# Sheet.net
KiCad netlist of a schematic drawn in Altium Designer
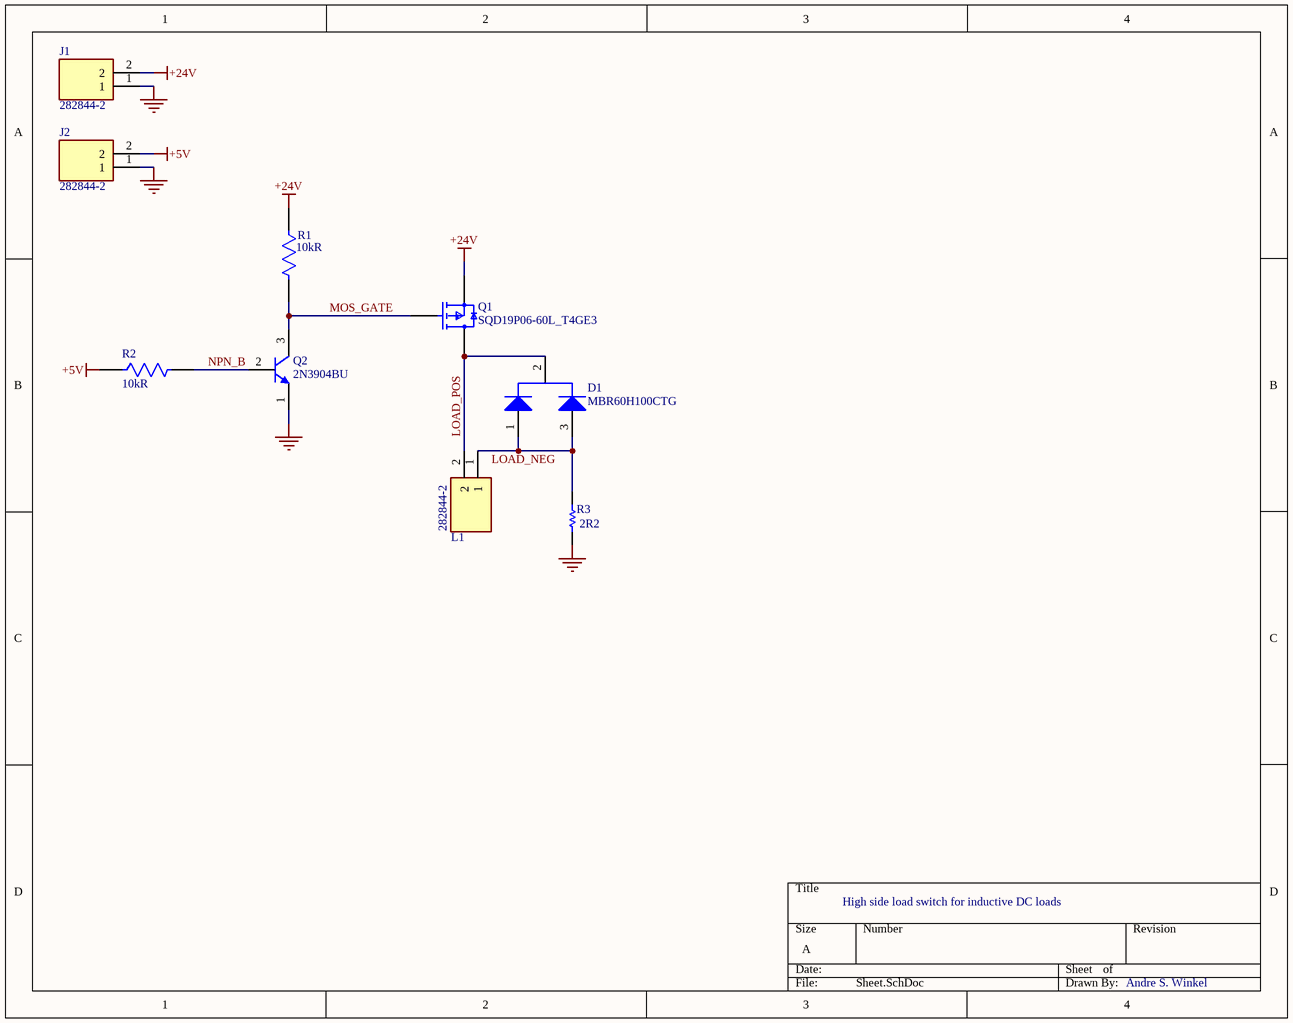
[diagram p0: Sheet.SchDoc]

(export (version "E")
  (design (tool "Eeschema 10.0.6"))
  (components
    (comp (ref "D1")
      (value "MBR60H100CTG")
      (footprint "ONSC-TO-220-3-221A-09_AF")
      (description "SWITCHMODE(TM) Power Rectifier, 100 V, 60 A, 3-Pin TO-220, Pb-Free, Tube")
      (fields (field (name "MANUFACTURER") "On Semiconductor"))
      (libsource (lib "Altium Content Vault") (part "ONSC-D-A1K2A3-3_B"))
    )
    (comp (ref "J1")
      (value "282844-2")
      (footprint "SamacSys:2828442")
      (description "Connector")
      (fields (field (name "MOUSER PART NUMBER") "571-282844-2"))
      (libsource (lib "") (part "282844-2_1"))
    )
    (comp (ref "J2")
      (value "282844-2")
      (footprint "SamacSys:2828442")
      (description "Connector")
      (fields (field (name "MOUSER PART NUMBER") "571-282844-2"))
      (libsource (lib "") (part "282844-2_1"))
    )
    (comp (ref "L1")
      (value "282844-2")
      (footprint "SamacSys:2828442")
      (description "Connector")
      (fields (field (name "MOUSER PART NUMBER") "571-282844-2"))
      (libsource (lib "*") (part "282844-2"))
    )
    (comp (ref "Q1")
      (value "SQD19P06-60L_T4GE3")
      (footprint "FP-T13-0592-MFG")
      (description "MOSFET P-CH 60V 20A TO252AA")
      (fields
        (field (name "OCTOPART") "https://octopart.com/sqd19p06-60l_t4ge3-vishay-82363551")
        (field (name "MANUFACTURER") "Vishay")
      )
      (libsource (lib "Altium Content Vault") (part "becdc239eb0611cc225413e84e4883d"))
    )
    (comp (ref "Q2")
      (value "2N3904BU")
      (footprint "FAIR-TO-92")
      (description "NPN General-Purpose Amplifier, 40 V VCEO, 0.2 A, -55 to 150 degC, 2-Pin TO-92, RoHS, Bulk")
      (fields (field (name "MANUFACTURER") "FairchildSemiconductor"))
      (libsource (lib "Altium Content Vault") (part "NPN-E1B2C3-3"))
    )
    (comp (ref "R1")
      (value "CRCW080510K0FKEA")
      (footprint "FP-CRCW0805-e3-IPC_A")
      (description "RES Thick Film, 10kΩ, 1%, 0.125W, 100ppm/°C, 0805")
      (fields (field (name "RESISTANCE") "10kR") (field (name "TOLERANCE") "1%"))
      (libsource (lib "Altium Content Vault") (part "1029c3af85768c4190bb7ad29bc67b5"))
    )
    (comp (ref "R2")
      (value "CRCW080510K0FKEA")
      (footprint "FP-CRCW0805-e3-IPC_A")
      (description "RES Thick Film, 10kΩ, 1%, 0.125W, 100ppm/°C, 0805")
      (fields (field (name "RESISTANCE") "10kR") (field (name "TOLERANCE") "1%"))
      (libsource (lib "Altium Content Vault") (part "1029c3af85768c4190bb7ad29bc67b5"))
    )
    (comp (ref "R3")
      (value "RC0402JR-072R2L")
      (footprint "RESC1005X40X25NL05T10")
      (fields (field (name "MANUFACTURER") "Yageo / Phycomp") (field (name "RESISTANCE") "2R2"))
      (libsource (lib "Altium Content Vault") (part "RES"))
    )
  )
  (nets
    (net (code "1") (name "+5V") (class "Default")
      (node (ref "J2") (pin "2") (pinfunction "2_2") (pintype "passive"))
      (node (ref "R2") (pin "1") (pinfunction "1_1") (pintype "passive"))
    )
    (net (code "2") (name "+24V") (class "Default")
      (node (ref "J1") (pin "2") (pinfunction "2_2") (pintype "passive"))
      (node (ref "Q1") (pin "3") (pinfunction "S_3") (pintype "passive"))
      (node (ref "R1") (pin "1") (pinfunction "1_1") (pintype "passive"))
    )
    (net (code "3") (name "/LOAD_NEG") (class "Default")
      (node (ref "D1") (pin "1") (pinfunction "A1_1") (pintype "passive"))
      (node (ref "D1") (pin "3") (pinfunction "A2_3") (pintype "passive"))
      (node (ref "L1") (pin "1") (pinfunction "1_1") (pintype "passive"))
      (node (ref "R3") (pin "1") (pinfunction "1_1") (pintype "passive"))
    )
    (net (code "4") (name "/LOAD_POS") (class "Default")
      (node (ref "D1") (pin "2") (pinfunction "K_2") (pintype "passive"))
      (node (ref "L1") (pin "2") (pinfunction "2_2") (pintype "passive"))
      (node (ref "Q1") (pin "4") (pinfunction "D_4") (pintype "passive"))
    )
    (net (code "5") (name "/MOS_GATE") (class "Default")
      (node (ref "Q1") (pin "1") (pinfunction "G_1") (pintype "passive"))
      (node (ref "Q2") (pin "3") (pinfunction "C_3") (pintype "passive"))
      (node (ref "R1") (pin "2") (pinfunction "2_2") (pintype "passive"))
    )
    (net (code "6") (name "/NPN_B") (class "Default")
      (node (ref "Q2") (pin "2") (pinfunction "B_2") (pintype "passive"))
      (node (ref "R2") (pin "2") (pinfunction "2_2") (pintype "passive"))
    )
    (net (code "7") (name "GND") (class "Default")
      (node (ref "J1") (pin "1") (pinfunction "1_1") (pintype "passive"))
      (node (ref "J2") (pin "1") (pinfunction "1_1") (pintype "passive"))
      (node (ref "Q2") (pin "1") (pinfunction "E_1") (pintype "passive"))
      (node (ref "R3") (pin "2") (pinfunction "2_2") (pintype "passive"))
    )
  )
)
